# board_power.net
KiCad netlist of a schematic drawn in EAGLE
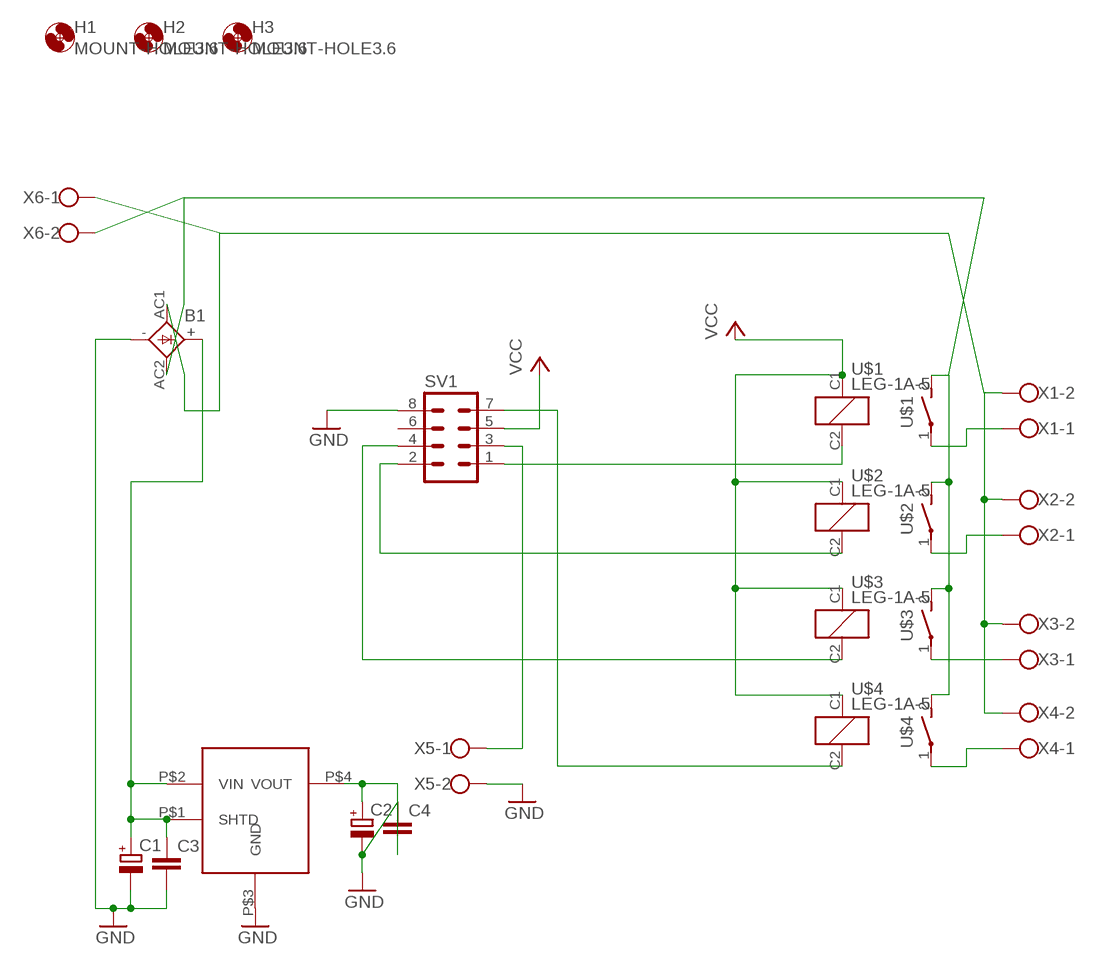
[diagram p0: schematic, sheet 1]

(export (version "E")
  (design (tool "Eeschema 10.0.6"))
  (components
    (comp (ref "B1")
      (value "KBK10A")
      (footprint "eagle-import:KBK10A")
      (libsource (lib "eagle-import") (part "KBK10A"))
    )
    (comp (ref "C1")
      (value "CPOL-EUE5-4")
      (footprint "eagle-import:E5-4")
      (libsource (lib "eagle-import") (part "CPOL-EUE5-4"))
    )
    (comp (ref "C2")
      (value "CPOL-EUE5-4")
      (footprint "eagle-import:E5-4")
      (libsource (lib "eagle-import") (part "CPOL-EUE5-4"))
    )
    (comp (ref "C3")
      (value "C-EU025_050-025X075")
      (footprint "eagle-import:C025_050-025X075")
      (libsource (lib "eagle-import") (part "C-EU025_050-025X075"))
    )
    (comp (ref "C4")
      (value "C-EU025_050-025X075")
      (footprint "eagle-import:C025_050-025X075")
      (libsource (lib "eagle-import") (part "C-EU025_050-025X075"))
    )
    (comp (ref "H1")
      (value "MOUNT-HOLE3.6")
      (footprint "eagle-import:3,6")
      (libsource (lib "eagle-import") (part "MOUNT-HOLE3.6"))
    )
    (comp (ref "H2")
      (value "MOUNT-HOLE3.6")
      (footprint "eagle-import:3,6")
      (libsource (lib "eagle-import") (part "MOUNT-HOLE3.6"))
    )
    (comp (ref "H3")
      (value "MOUNT-HOLE3.6")
      (footprint "eagle-import:3,6")
      (libsource (lib "eagle-import") (part "MOUNT-HOLE3.6"))
    )
    (comp (ref "SV1")
      (value "MA04-2")
      (footprint "eagle-import:MA04-2")
      (libsource (lib "eagle-import") (part "MA04-2"))
    )
    (comp (ref "U$1")
      (value "LEG-1A-5")
      (footprint "eagle-import:LEG")
      (libsource (lib "eagle-import") (part "LEG-1A-5"))
    )
    (comp (ref "U$2")
      (value "LEG-1A-5")
      (footprint "eagle-import:LEG")
      (libsource (lib "eagle-import") (part "LEG-1A-5"))
    )
    (comp (ref "U$3")
      (value "LEG-1A-5")
      (footprint "eagle-import:LEG")
      (libsource (lib "eagle-import") (part "LEG-1A-5"))
    )
    (comp (ref "U$4")
      (value "LEG-1A-5")
      (footprint "eagle-import:LEG")
      (libsource (lib "eagle-import") (part "LEG-1A-5"))
    )
    (comp (ref "U$5")
      (value "POLOLU-2098")
      (footprint "eagle-import:POLOLU-2098")
      (libsource (lib "eagle-import") (part "POLOLU-2098"))
    )
    (comp (ref "X1")
      (value "PASSO3")
      (footprint "eagle-import:PASSO3")
      (fields (field (name "MPN") "237-102"))
      (libsource (lib "eagle-import") (part "PASSO3"))
    )
    (comp (ref "X2")
      (value "PASSO3")
      (footprint "eagle-import:PASSO3")
      (fields (field (name "MPN") "237-102"))
      (libsource (lib "eagle-import") (part "PASSO3"))
    )
    (comp (ref "X3")
      (value "PASSO3")
      (footprint "eagle-import:PASSO3")
      (fields (field (name "MPN") "237-102"))
      (libsource (lib "eagle-import") (part "PASSO3"))
    )
    (comp (ref "X4")
      (value "PASSO3")
      (footprint "eagle-import:PASSO3")
      (fields (field (name "MPN") "237-102"))
      (libsource (lib "eagle-import") (part "PASSO3"))
    )
    (comp (ref "X5")
      (value "PASSO3")
      (footprint "eagle-import:PASSO3")
      (fields (field (name "MPN") "237-102"))
      (libsource (lib "eagle-import") (part "PASSO3"))
    )
    (comp (ref "X6")
      (value "PASSO3")
      (footprint "eagle-import:PASSO3")
      (fields (field (name "MPN") "237-102"))
      (libsource (lib "eagle-import") (part "PASSO3"))
    )
  )
  (nets
    (net (code "1") (name "GND") (class "Default")
      (node (ref "B1") (pin "-") (pinfunction "-_-") (pintype "passive"))
      (node (ref "C1") (pin "-") (pinfunction "-_-") (pintype "passive"))
      (node (ref "C2") (pin "-") (pinfunction "-_-") (pintype "passive"))
      (node (ref "C3") (pin "2") (pinfunction "2_2") (pintype "passive"))
      (node (ref "C4") (pin "1") (pinfunction "1_1") (pintype "passive"))
      (node (ref "SV1") (pin "8") (pinfunction "8_8") (pintype "passive"))
      (node (ref "U$5") (pin "P$3") (pinfunction "GND_P$3") (pintype "bidirectional"))
      (node (ref "X5") (pin "2") (pinfunction "KL_2") (pintype "passive"))
    )
    (net (code "2") (name "Net-(U$1A-P)") (class "Default")
      (node (ref "U$1") (pin "1") (pinfunction "P_1") (pintype "passive"))
      (node (ref "X1") (pin "1") (pinfunction "KL_1") (pintype "passive"))
    )
    (net (code "3") (name "Net-(U$1A-S)") (class "Default")
      (node (ref "B1") (pin "AC2") (pinfunction "AC2_AC2") (pintype "passive"))
      (node (ref "U$1") (pin "2") (pinfunction "S_2") (pintype "passive"))
      (node (ref "U$2") (pin "2") (pinfunction "S_2") (pintype "passive"))
      (node (ref "U$3") (pin "2") (pinfunction "S_2") (pintype "passive"))
      (node (ref "U$4") (pin "2") (pinfunction "S_2") (pintype "passive"))
      (node (ref "X6") (pin "2") (pinfunction "KL_2") (pintype "passive"))
    )
    (net (code "4") (name "Net-(U$1B-2)") (class "Default")
      (node (ref "SV1") (pin "1") (pinfunction "1_1") (pintype "passive"))
      (node (ref "U$1") (pin "C2") (pinfunction "2_C2") (pintype "passive"))
    )
    (net (code "5") (name "Net-(U$2A-P)") (class "Default")
      (node (ref "U$2") (pin "1") (pinfunction "P_1") (pintype "passive"))
      (node (ref "X2") (pin "1") (pinfunction "KL_1") (pintype "passive"))
    )
    (net (code "6") (name "Net-(U$2B-2)") (class "Default")
      (node (ref "SV1") (pin "2") (pinfunction "2_2") (pintype "passive"))
      (node (ref "U$2") (pin "C2") (pinfunction "2_C2") (pintype "passive"))
    )
    (net (code "7") (name "Net-(U$3A-P)") (class "Default")
      (node (ref "U$3") (pin "1") (pinfunction "P_1") (pintype "passive"))
      (node (ref "X3") (pin "1") (pinfunction "KL_1") (pintype "passive"))
    )
    (net (code "8") (name "Net-(U$3B-2)") (class "Default")
      (node (ref "SV1") (pin "4") (pinfunction "4_4") (pintype "passive"))
      (node (ref "U$3") (pin "C2") (pinfunction "2_C2") (pintype "passive"))
    )
    (net (code "9") (name "Net-(U$4A-P)") (class "Default")
      (node (ref "U$4") (pin "1") (pinfunction "P_1") (pintype "passive"))
      (node (ref "X4") (pin "1") (pinfunction "KL_1") (pintype "passive"))
    )
    (net (code "10") (name "Net-(U$4B-2)") (class "Default")
      (node (ref "SV1") (pin "7") (pinfunction "7_7") (pintype "passive"))
      (node (ref "U$4") (pin "C2") (pinfunction "2_C2") (pintype "passive"))
    )
    (net (code "11") (name "Net-(U$5-SHTD)") (class "Default")
      (node (ref "B1") (pin "+") (pinfunction "+_+") (pintype "passive"))
      (node (ref "C1") (pin "+") (pinfunction "+_+") (pintype "passive"))
      (node (ref "C3") (pin "1") (pinfunction "1_1") (pintype "passive"))
      (node (ref "U$5") (pin "P$1") (pinfunction "SHTD_P$1") (pintype "power_in"))
      (node (ref "U$5") (pin "P$2") (pinfunction "VIN_P$2") (pintype "power_in"))
    )
    (net (code "12") (name "Net-(U$5-VOUT)") (class "Default")
      (node (ref "C2") (pin "+") (pinfunction "+_+") (pintype "passive"))
      (node (ref "C4") (pin "2") (pinfunction "2_2") (pintype "passive"))
      (node (ref "U$5") (pin "P$4") (pinfunction "VOUT_P$4") (pintype "bidirectional"))
    )
    (net (code "13") (name "Net-(X1B-KL)") (class "Default")
      (node (ref "B1") (pin "AC1") (pinfunction "AC1_AC1") (pintype "passive"))
      (node (ref "X1") (pin "2") (pinfunction "KL_2") (pintype "passive"))
      (node (ref "X2") (pin "2") (pinfunction "KL_2") (pintype "passive"))
      (node (ref "X3") (pin "2") (pinfunction "KL_2") (pintype "passive"))
      (node (ref "X4") (pin "2") (pinfunction "KL_2") (pintype "passive"))
      (node (ref "X6") (pin "1") (pinfunction "KL_1") (pintype "passive"))
    )
    (net (code "14") (name "Net-(X5A-KL)") (class "Default")
      (node (ref "SV1") (pin "3") (pinfunction "3_3") (pintype "passive"))
      (node (ref "X5") (pin "1") (pinfunction "KL_1") (pintype "passive"))
    )
    (net (code "15") (name "VCC") (class "Default")
      (node (ref "SV1") (pin "5") (pinfunction "5_5") (pintype "passive"))
      (node (ref "U$1") (pin "C1") (pinfunction "1_C1") (pintype "passive"))
      (node (ref "U$2") (pin "C1") (pinfunction "1_C1") (pintype "passive"))
      (node (ref "U$3") (pin "C1") (pinfunction "1_C1") (pintype "passive"))
      (node (ref "U$4") (pin "C1") (pinfunction "1_C1") (pintype "passive"))
    )
    (net (code "16") (name "unconnected-(SV1-Pad6)") (class "Default")
      (node (ref "SV1") (pin "6") (pinfunction "6_6") (pintype "passive"))
    )
  )
)
